# Controller.net
KiCad netlist of a schematic drawn in EAGLE
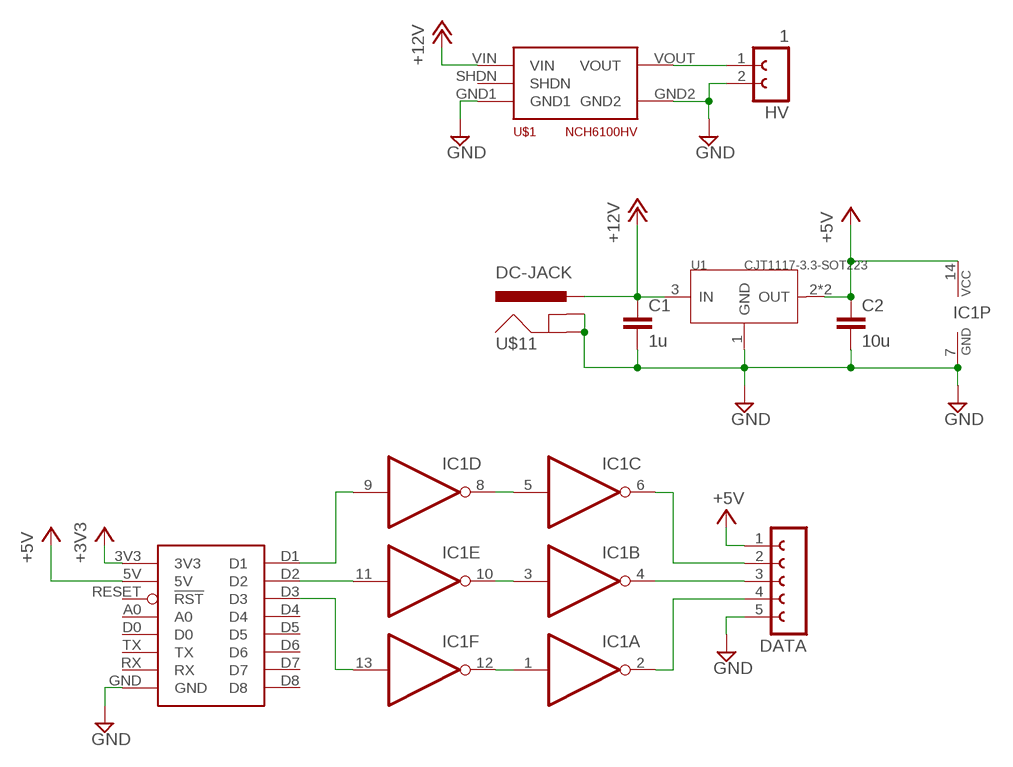
[diagram p0: schematic, sheet 1]

(export (version "E")
  (design (tool "Eeschema 10.0.6"))
  (components
    (comp (ref "C1")
      (value "1u")
      (footprint "eagle-import:C0603K")
      (libsource (lib "eagle-import") (part "C-EUC0603K"))
    )
    (comp (ref "C2")
      (value "10u")
      (footprint "eagle-import:C0603K")
      (libsource (lib "eagle-import") (part "C-EUC0603K"))
    )
    (comp (ref "DATA")
      (value "FE05W")
      (footprint "eagle-import:FE05W")
      (libsource (lib "eagle-import") (part "FE05W"))
    )
    (comp (ref "HV")
      (value "1")
      (footprint "eagle-import:FE02W")
      (libsource (lib "eagle-import") (part "FE02W"))
    )
    (comp (ref "IC1")
      (value "74HCT04D")
      (footprint "eagle-import:SO-14")
      (libsource (lib "eagle-import") (part "74HCT04D"))
    )
    (comp (ref "U$1")
      (value "NCH6100HV")
      (footprint "eagle-import:NCH6100HV")
      (libsource (lib "eagle-import") (part "NCH6100HV"))
    )
    (comp (ref "U$11")
      (value "DC-JACK")
      (footprint "eagle-import:POWER_JACK_PTH")
      (libsource (lib "eagle-import") (part "DC-JACK"))
    )
    (comp (ref "U$12")
      (value "WEMOS-D1")
      (footprint "eagle-import:WEMOS-D1-MINI")
      (libsource (lib "eagle-import") (part "WEMOS-D1"))
    )
    (comp (ref "U1")
      (value "CJT1117-3.3-SOT223")
      (footprint "eagle-import:SOT-223")
      (fields (field (name "MPN") "CJT1117-3.3"))
      (libsource (lib "eagle-import") (part "PMIC-CJT1117-3.3(SOT223)"))
    )
  )
  (nets
    (net (code "1") (name "+3V3") (class "Default")
      (node (ref "U$12") (pin "3V3") (pinfunction "3V3_3V3") (pintype "power_in"))
    )
    (net (code "2") (name "+5V") (class "Default")
      (node (ref "C2") (pin "1") (pinfunction "1_1") (pintype "passive"))
      (node (ref "DATA") (pin "1") (pinfunction "1_1") (pintype "passive"))
      (node (ref "IC1") (pin "14") (pinfunction "VCC_14") (pintype "power_in"))
      (node (ref "U$12") (pin "5V") (pinfunction "5V_5V") (pintype "power_in"))
      (node (ref "U1") (pin "2") (pinfunction "OUT_2") (pintype "bidirectional"))
      (node (ref "U1") (pin "TER") (pinfunction "OUT_TER") (pintype "bidirectional"))
    )
    (net (code "3") (name "+12V") (class "Default")
      (node (ref "C1") (pin "1") (pinfunction "1_1") (pintype "passive"))
      (node (ref "U$1") (pin "VIN") (pinfunction "VIN_VIN") (pintype "power_in"))
      (node (ref "U$11") (pin "PWR") (pinfunction "PWR_PWR") (pintype "bidirectional"))
      (node (ref "U1") (pin "3") (pinfunction "IN_3") (pintype "bidirectional"))
    )
    (net (code "4") (name "GND") (class "Default")
      (node (ref "C1") (pin "2") (pinfunction "2_2") (pintype "passive"))
      (node (ref "C2") (pin "2") (pinfunction "2_2") (pintype "passive"))
      (node (ref "DATA") (pin "5") (pinfunction "5_5") (pintype "passive"))
      (node (ref "HV") (pin "2") (pinfunction "2_2") (pintype "passive"))
      (node (ref "IC1") (pin "7") (pinfunction "GND_7") (pintype "power_in"))
      (node (ref "U$1") (pin "GND1") (pinfunction "GND1_GND1") (pintype "power_in"))
      (node (ref "U$1") (pin "GND2") (pinfunction "GND2_GND2") (pintype "power_in"))
      (node (ref "U$11") (pin "GND") (pinfunction "GND_GND") (pintype "bidirectional"))
      (node (ref "U$11") (pin "GNDBREAK") (pinfunction "GNDBREAK_GNDBREAK") (pintype "bidirectional"))
      (node (ref "U$12") (pin "GND") (pinfunction "GND_GND") (pintype "power_in"))
      (node (ref "U1") (pin "1") (pinfunction "GND_1") (pintype "bidirectional"))
    )
    (net (code "5") (name "Net-(HV-Pad1)") (class "Default")
      (node (ref "HV") (pin "1") (pinfunction "1_1") (pintype "passive"))
      (node (ref "U$1") (pin "VOUT") (pinfunction "VOUT_VOUT") (pintype "bidirectional"))
    )
    (net (code "6") (name "Net-(IC1A-I)") (class "Default")
      (node (ref "IC1") (pin "1") (pinfunction "I_1") (pintype "input"))
      (node (ref "IC1") (pin "12") (pinfunction "O_12") (pintype "output"))
    )
    (net (code "7") (name "Net-(IC1A-O)") (class "Default")
      (node (ref "DATA") (pin "4") (pinfunction "4_4") (pintype "passive"))
      (node (ref "IC1") (pin "2") (pinfunction "O_2") (pintype "output"))
    )
    (net (code "8") (name "Net-(IC1B-I)") (class "Default")
      (node (ref "IC1") (pin "10") (pinfunction "O_10") (pintype "output"))
      (node (ref "IC1") (pin "3") (pinfunction "I_3") (pintype "input"))
    )
    (net (code "9") (name "Net-(IC1B-O)") (class "Default")
      (node (ref "DATA") (pin "3") (pinfunction "3_3") (pintype "passive"))
      (node (ref "IC1") (pin "4") (pinfunction "O_4") (pintype "output"))
    )
    (net (code "10") (name "Net-(IC1C-I)") (class "Default")
      (node (ref "IC1") (pin "5") (pinfunction "I_5") (pintype "input"))
      (node (ref "IC1") (pin "8") (pinfunction "O_8") (pintype "output"))
    )
    (net (code "11") (name "Net-(IC1C-O)") (class "Default")
      (node (ref "DATA") (pin "2") (pinfunction "2_2") (pintype "passive"))
      (node (ref "IC1") (pin "6") (pinfunction "O_6") (pintype "output"))
    )
    (net (code "12") (name "Net-(IC1D-I)") (class "Default")
      (node (ref "IC1") (pin "9") (pinfunction "I_9") (pintype "input"))
      (node (ref "U$12") (pin "D1") (pinfunction "D1_D1") (pintype "bidirectional"))
    )
    (net (code "13") (name "Net-(IC1E-I)") (class "Default")
      (node (ref "IC1") (pin "11") (pinfunction "I_11") (pintype "input"))
      (node (ref "U$12") (pin "D2") (pinfunction "D2_D2") (pintype "bidirectional"))
    )
    (net (code "14") (name "Net-(IC1F-I)") (class "Default")
      (node (ref "IC1") (pin "13") (pinfunction "I_13") (pintype "input"))
      (node (ref "U$12") (pin "D3") (pinfunction "D3_D3") (pintype "bidirectional"))
    )
    (net (code "15") (name "unconnected-(U$1-PadSHDN)") (class "Default")
      (node (ref "U$1") (pin "SHDN") (pinfunction "SHDN_SHDN") (pintype "input"))
    )
    (net (code "16") (name "unconnected-(U$12-PadA0)") (class "Default")
      (node (ref "U$12") (pin "A0") (pinfunction "A0_A0") (pintype "bidirectional"))
    )
    (net (code "17") (name "unconnected-(U$12-PadD0)") (class "Default")
      (node (ref "U$12") (pin "D0") (pinfunction "D0_D0") (pintype "bidirectional"))
    )
    (net (code "18") (name "unconnected-(U$12-PadD4)") (class "Default")
      (node (ref "U$12") (pin "D4") (pinfunction "D4_D4") (pintype "bidirectional"))
    )
    (net (code "19") (name "unconnected-(U$12-PadD5)") (class "Default")
      (node (ref "U$12") (pin "D5") (pinfunction "D5_D5") (pintype "bidirectional"))
    )
    (net (code "20") (name "unconnected-(U$12-PadD6)") (class "Default")
      (node (ref "U$12") (pin "D6") (pinfunction "D6_D6") (pintype "bidirectional"))
    )
    (net (code "21") (name "unconnected-(U$12-PadD7)") (class "Default")
      (node (ref "U$12") (pin "D7") (pinfunction "D7_D7") (pintype "bidirectional"))
    )
    (net (code "22") (name "unconnected-(U$12-PadD8)") (class "Default")
      (node (ref "U$12") (pin "D8") (pinfunction "D8_D8") (pintype "bidirectional"))
    )
    (net (code "23") (name "unconnected-(U$12-PadRX)") (class "Default")
      (node (ref "U$12") (pin "RX") (pinfunction "RX_RX") (pintype "input"))
    )
    (net (code "24") (name "unconnected-(U$12-PadTX)") (class "Default")
      (node (ref "U$12") (pin "TX") (pinfunction "TX_TX") (pintype "output"))
    )
    (net (code "25") (name "unconnected-(U$12-~{RST}-PadRESET)") (class "Default")
      (node (ref "U$12") (pin "RESET") (pinfunction "~{RST}_RESET") (pintype "input"))
    )
  )
)
